# Voltage_Sense_Unit.net
KiCad netlist of a schematic drawn in Altium Designer
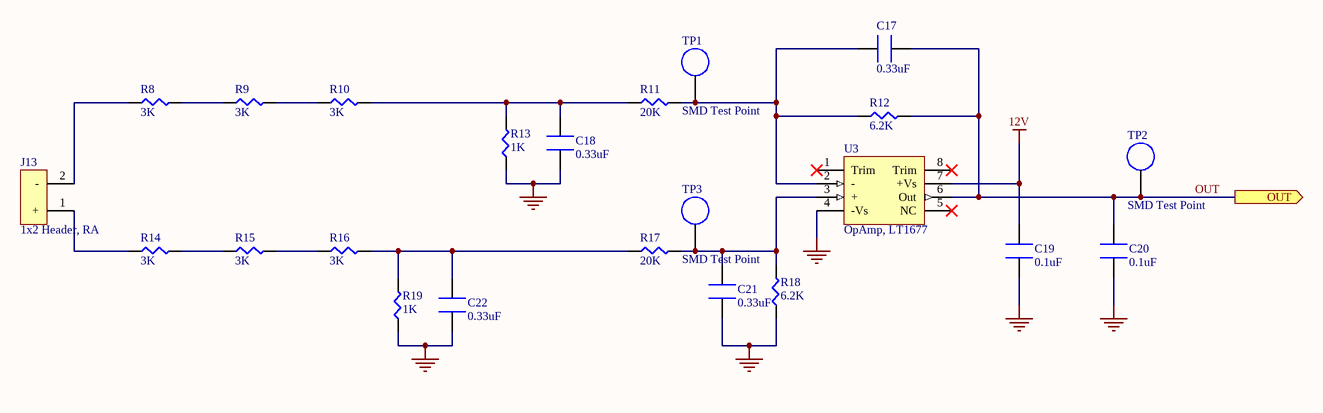
[diagram p0: Voltage Sense Unit.SchDoc]

(export (version "E")
  (design (tool "Eeschema 10.0.6"))
  (components
    (comp (ref "C17")
      (value "0.33uF")
      (footprint "C0805")
      (description "CAP CER 0.33UF 50V X7R 0805")
      (fields
        (field (name "MANUFACTURER") "Samsung")
        (field (name "MANUFACTURER PART NUMBER") "CL21B334KBFVPNE")
      )
      (libsource (lib "ASB") (part "CL21B334KBFVPNE"))
    )
    (comp (ref "C18")
      (value "0.33uF")
      (footprint "C0805")
      (description "CAP CER 0.33UF 50V X7R 0805")
      (fields
        (field (name "MANUFACTURER") "Samsung")
        (field (name "MANUFACTURER PART NUMBER") "CL21B334KBFVPNE")
      )
      (libsource (lib "ASB") (part "CL21B334KBFVPNE"))
    )
    (comp (ref "C19")
      (value "0.1uF")
      (footprint "C0805")
      (description "CAP CER 0.1UF 50V X7R 0805")
      (fields
        (field (name "MANUFACTURER") "Samsung")
        (field (name "MANUFACTURER PART NUMBER") "CL21B104KBCWPNC")
      )
      (libsource (lib "ASB") (part "CL21B104KBCWPNC"))
    )
    (comp (ref "C20")
      (value "0.1uF")
      (footprint "C0805")
      (description "CAP CER 0.1UF 50V X7R 0805")
      (fields
        (field (name "MANUFACTURER") "Samsung")
        (field (name "MANUFACTURER PART NUMBER") "CL21B104KBCWPNC")
      )
      (libsource (lib "ASB") (part "CL21B104KBCWPNC"))
    )
    (comp (ref "C21")
      (value "0.33uF")
      (footprint "C0805")
      (description "CAP CER 0.33UF 50V X7R 0805")
      (fields
        (field (name "MANUFACTURER") "Samsung")
        (field (name "MANUFACTURER PART NUMBER") "CL21B334KBFVPNE")
      )
      (libsource (lib "ASB") (part "CL21B334KBFVPNE"))
    )
    (comp (ref "C22")
      (value "0.33uF")
      (footprint "C0805")
      (description "CAP CER 0.33UF 50V X7R 0805")
      (fields
        (field (name "MANUFACTURER") "Samsung")
        (field (name "MANUFACTURER PART NUMBER") "CL21B334KBFVPNE")
      )
      (libsource (lib "ASB") (part "CL21B334KBFVPNE"))
    )
    (comp (ref "J13")
      (value "1x2 Header, RA")
      (footprint "Right Angle Header 43650-0205(Primary)")
      (description "HEADER, RIGHT ANGLE, 2WAY")
      (fields (field (name "MANUFACTURER") "Molex") (field (name "MANUFACTURER PART NUMBER") "43650-0205"))
      (libsource (lib "ASB") (part "43650-0205"))
    )
    (comp (ref "R8")
      (value "3K")
      (footprint "R0805")
      (description "RES SMD 3K OHM 1% 1/8W 0805")
      (fields
        (field (name "MANUFACTURER") "Panasonic")
        (field (name "MANUFACTURER PART NUMBER") "ERJ6ENF3001V")
      )
      (libsource (lib "ASB") (part "ERJ6ENF3001V"))
    )
    (comp (ref "R9")
      (value "3K")
      (footprint "R0805")
      (description "RES SMD 3K OHM 1% 1/8W 0805")
      (fields
        (field (name "MANUFACTURER") "Panasonic")
        (field (name "MANUFACTURER PART NUMBER") "ERJ6ENF3001V")
      )
      (libsource (lib "ASB") (part "ERJ6ENF3001V"))
    )
    (comp (ref "R10")
      (value "3K")
      (footprint "R0805")
      (description "RES SMD 3K OHM 1% 1/8W 0805")
      (fields
        (field (name "MANUFACTURER") "Panasonic")
        (field (name "MANUFACTURER PART NUMBER") "ERJ6ENF3001V")
      )
      (libsource (lib "ASB") (part "ERJ6ENF3001V"))
    )
    (comp (ref "R11")
      (value "20K")
      (footprint "R0805")
      (description "RES SMD 20K OHM 1% 1/8W 0805")
      (fields
        (field (name "MANUFACTURER") "Panasonic")
        (field (name "MANUFACTURER PART NUMBER") "ERJ6ENF2002V")
      )
      (libsource (lib "ASB") (part "ERJ6ENF2002V"))
    )
    (comp (ref "R12")
      (value "6.2K")
      (footprint "R0805")
      (description "RES SMD 6.2K OHM 1% 1/8W 0805")
      (fields
        (field (name "MANUFACTURER") "Panasonic")
        (field (name "MANUFACTURER PART NUMBER") "ERJ6ENF6201V")
      )
      (libsource (lib "ASB") (part "ERJ6ENF6201V"))
    )
    (comp (ref "R13")
      (value "1K")
      (footprint "R0805")
      (description "RES SMD 1K OHM 1% 1/8W 0805")
      (fields
        (field (name "MANUFACTURER") "Panasonic")
        (field (name "MANUFACTURER PART NUMBER") "ERJ6ENF1001V")
      )
      (libsource (lib "ASB") (part "ERJ6ENF1001V"))
    )
    (comp (ref "R14")
      (value "3K")
      (footprint "R0805")
      (description "RES SMD 3K OHM 1% 1/8W 0805")
      (fields
        (field (name "MANUFACTURER") "Panasonic")
        (field (name "MANUFACTURER PART NUMBER") "ERJ6ENF3001V")
      )
      (libsource (lib "ASB") (part "ERJ6ENF3001V"))
    )
    (comp (ref "R15")
      (value "3K")
      (footprint "R0805")
      (description "RES SMD 3K OHM 1% 1/8W 0805")
      (fields
        (field (name "MANUFACTURER") "Panasonic")
        (field (name "MANUFACTURER PART NUMBER") "ERJ6ENF3001V")
      )
      (libsource (lib "ASB") (part "ERJ6ENF3001V"))
    )
    (comp (ref "R16")
      (value "3K")
      (footprint "R0805")
      (description "RES SMD 3K OHM 1% 1/8W 0805")
      (fields
        (field (name "MANUFACTURER") "Panasonic")
        (field (name "MANUFACTURER PART NUMBER") "ERJ6ENF3001V")
      )
      (libsource (lib "ASB") (part "ERJ6ENF3001V"))
    )
    (comp (ref "R17")
      (value "20K")
      (footprint "R0805")
      (description "RES SMD 20K OHM 1% 1/8W 0805")
      (fields
        (field (name "MANUFACTURER") "Panasonic")
        (field (name "MANUFACTURER PART NUMBER") "ERJ6ENF2002V")
      )
      (libsource (lib "ASB") (part "ERJ6ENF2002V"))
    )
    (comp (ref "R18")
      (value "6.2K")
      (footprint "R0805")
      (description "RES SMD 6.2K OHM 1% 1/8W 0805")
      (fields
        (field (name "MANUFACTURER") "Panasonic")
        (field (name "MANUFACTURER PART NUMBER") "ERJ6ENF6201V")
      )
      (libsource (lib "ASB") (part "ERJ6ENF6201V"))
    )
    (comp (ref "R19")
      (value "1K")
      (footprint "R0805")
      (description "RES SMD 1K OHM 1% 1/8W 0805")
      (fields
        (field (name "MANUFACTURER") "Panasonic")
        (field (name "MANUFACTURER PART NUMBER") "ERJ6ENF1001V")
      )
      (libsource (lib "ASB") (part "ERJ6ENF1001V"))
    )
    (comp (ref "TP1")
      (value "SMD Test Point")
      (footprint "5019 Keystone SMT Test Point")
      (description "Phosphor Bronze Contact Miniature Silver Plated Surface Mount Test Points")
      (fields
        (field (name "MANUFACTURER") "Keystone Electronics")
        (field (name "MANUFACTURER PART NUMBER") "5019")
      )
      (libsource (lib "ASB") (part "5019"))
    )
    (comp (ref "TP2")
      (value "SMD Test Point")
      (footprint "5019 Keystone SMT Test Point")
      (description "Phosphor Bronze Contact Miniature Silver Plated Surface Mount Test Points")
      (fields
        (field (name "MANUFACTURER") "Keystone Electronics")
        (field (name "MANUFACTURER PART NUMBER") "5019")
      )
      (libsource (lib "ASB") (part "5019"))
    )
    (comp (ref "TP3")
      (value "SMD Test Point")
      (footprint "5019 Keystone SMT Test Point")
      (description "Phosphor Bronze Contact Miniature Silver Plated Surface Mount Test Points")
      (fields
        (field (name "MANUFACTURER") "Keystone Electronics")
        (field (name "MANUFACTURER PART NUMBER") "5019")
      )
      (libsource (lib "ASB") (part "5019"))
    )
    (comp (ref "U3")
      (value "OpAmp, LT1677")
      (footprint "LT1677IS8#TRPBF")
      (description "IC OPAMP GP 7.2MHZ RRO 8SO")
      (fields
        (field (name "MANUFACTURER") "Analog Devices / Linear Technology")
        (field (name "MANUFACTURER PART NUMBER") "LT1677IS8#TRPBF")
      )
      (libsource (lib "ASB") (part "LT1677IS8#TRPBF"))
    )
  )
  (nets
    (net (code "1") (name "/OUT") (class "Default")
      (node (ref "C17") (pin "2") (pinfunction "2_2") (pintype "passive"))
      (node (ref "C20") (pin "2") (pinfunction "2_2") (pintype "passive"))
      (node (ref "R12") (pin "2") (pinfunction "2_2") (pintype "passive"))
      (node (ref "TP2") (pin "1") (pinfunction "1_1") (pintype "passive"))
      (node (ref "U3") (pin "6") (pinfunction "Out_6") (pintype "output"))
    )
    (net (code "2") (name "12V") (class "Default")
      (node (ref "C19") (pin "2") (pinfunction "2_2") (pintype "passive"))
      (node (ref "U3") (pin "7") (pinfunction "+Vs_7") (pintype "power_in"))
    )
    (net (code "3") (name "GND") (class "Default")
      (node (ref "C18") (pin "1") (pinfunction "1_1") (pintype "passive"))
      (node (ref "C19") (pin "1") (pinfunction "1_1") (pintype "passive"))
      (node (ref "C20") (pin "1") (pinfunction "1_1") (pintype "passive"))
      (node (ref "C21") (pin "1") (pinfunction "1_1") (pintype "passive"))
      (node (ref "C22") (pin "1") (pinfunction "1_1") (pintype "passive"))
      (node (ref "R13") (pin "1") (pinfunction "1_1") (pintype "passive"))
      (node (ref "R18") (pin "1") (pinfunction "1_1") (pintype "passive"))
      (node (ref "R19") (pin "1") (pinfunction "1_1") (pintype "passive"))
      (node (ref "U3") (pin "4") (pinfunction "-Vs_4") (pintype "power_in"))
    )
    (net (code "4") (name "Net-(C18-Pad2)") (class "Default")
      (node (ref "C18") (pin "2") (pinfunction "2_2") (pintype "passive"))
      (node (ref "R10") (pin "2") (pinfunction "2_2") (pintype "passive"))
      (node (ref "R11") (pin "1") (pinfunction "1_1") (pintype "passive"))
      (node (ref "R13") (pin "2") (pinfunction "2_2") (pintype "passive"))
    )
    (net (code "5") (name "Net-(C22-Pad2)") (class "Default")
      (node (ref "C22") (pin "2") (pinfunction "2_2") (pintype "passive"))
      (node (ref "R16") (pin "2") (pinfunction "2_2") (pintype "passive"))
      (node (ref "R17") (pin "1") (pinfunction "1_1") (pintype "passive"))
      (node (ref "R19") (pin "2") (pinfunction "2_2") (pintype "passive"))
    )
    (net (code "6") (name "Net-(J13-+)") (class "Default")
      (node (ref "J13") (pin "1") (pinfunction "+_1") (pintype "passive"))
      (node (ref "R14") (pin "1") (pinfunction "1_1") (pintype "passive"))
    )
    (net (code "7") (name "Net-(J13--)") (class "Default")
      (node (ref "J13") (pin "2") (pinfunction "-_2") (pintype "passive"))
      (node (ref "R8") (pin "1") (pinfunction "1_1") (pintype "passive"))
    )
    (net (code "8") (name "Net-(R8-Pad2)") (class "Default")
      (node (ref "R8") (pin "2") (pinfunction "2_2") (pintype "passive"))
      (node (ref "R9") (pin "1") (pinfunction "1_1") (pintype "passive"))
    )
    (net (code "9") (name "Net-(R10-Pad1)") (class "Default")
      (node (ref "R10") (pin "1") (pinfunction "1_1") (pintype "passive"))
      (node (ref "R9") (pin "2") (pinfunction "2_2") (pintype "passive"))
    )
    (net (code "10") (name "Net-(R14-Pad2)") (class "Default")
      (node (ref "R14") (pin "2") (pinfunction "2_2") (pintype "passive"))
      (node (ref "R15") (pin "1") (pinfunction "1_1") (pintype "passive"))
    )
    (net (code "11") (name "Net-(R15-Pad2)") (class "Default")
      (node (ref "R15") (pin "2") (pinfunction "2_2") (pintype "passive"))
      (node (ref "R16") (pin "1") (pinfunction "1_1") (pintype "passive"))
    )
    (net (code "12") (name "Net-(U3-+)") (class "Default")
      (node (ref "C21") (pin "2") (pinfunction "2_2") (pintype "passive"))
      (node (ref "R17") (pin "2") (pinfunction "2_2") (pintype "passive"))
      (node (ref "R18") (pin "2") (pinfunction "2_2") (pintype "passive"))
      (node (ref "TP3") (pin "1") (pinfunction "1_1") (pintype "passive"))
      (node (ref "U3") (pin "3") (pinfunction "+_3") (pintype "input"))
    )
    (net (code "13") (name "Net-(U3--)") (class "Default")
      (node (ref "C17") (pin "1") (pinfunction "1_1") (pintype "passive"))
      (node (ref "R11") (pin "2") (pinfunction "2_2") (pintype "passive"))
      (node (ref "R12") (pin "1") (pinfunction "1_1") (pintype "passive"))
      (node (ref "TP1") (pin "1") (pinfunction "1_1") (pintype "passive"))
      (node (ref "U3") (pin "2") (pinfunction "-_2") (pintype "input"))
    )
    (net (code "14") (name "unconnected-(U3-NC-Pad5)") (class "Default")
      (node (ref "U3") (pin "5") (pinfunction "NC_5") (pintype "passive+no_connect"))
    )
    (net (code "15") (name "unconnected-(U3-Trim-Pad1)") (class "Default")
      (node (ref "U3") (pin "1") (pinfunction "Trim_1") (pintype "passive+no_connect"))
    )
    (net (code "16") (name "unconnected-(U3-Trim-Pad8)") (class "Default")
      (node (ref "U3") (pin "8") (pinfunction "Trim_8") (pintype "passive+no_connect"))
    )
  )
)
